# P08R60.net
KiCad netlist of a schematic drawn in EAGLE
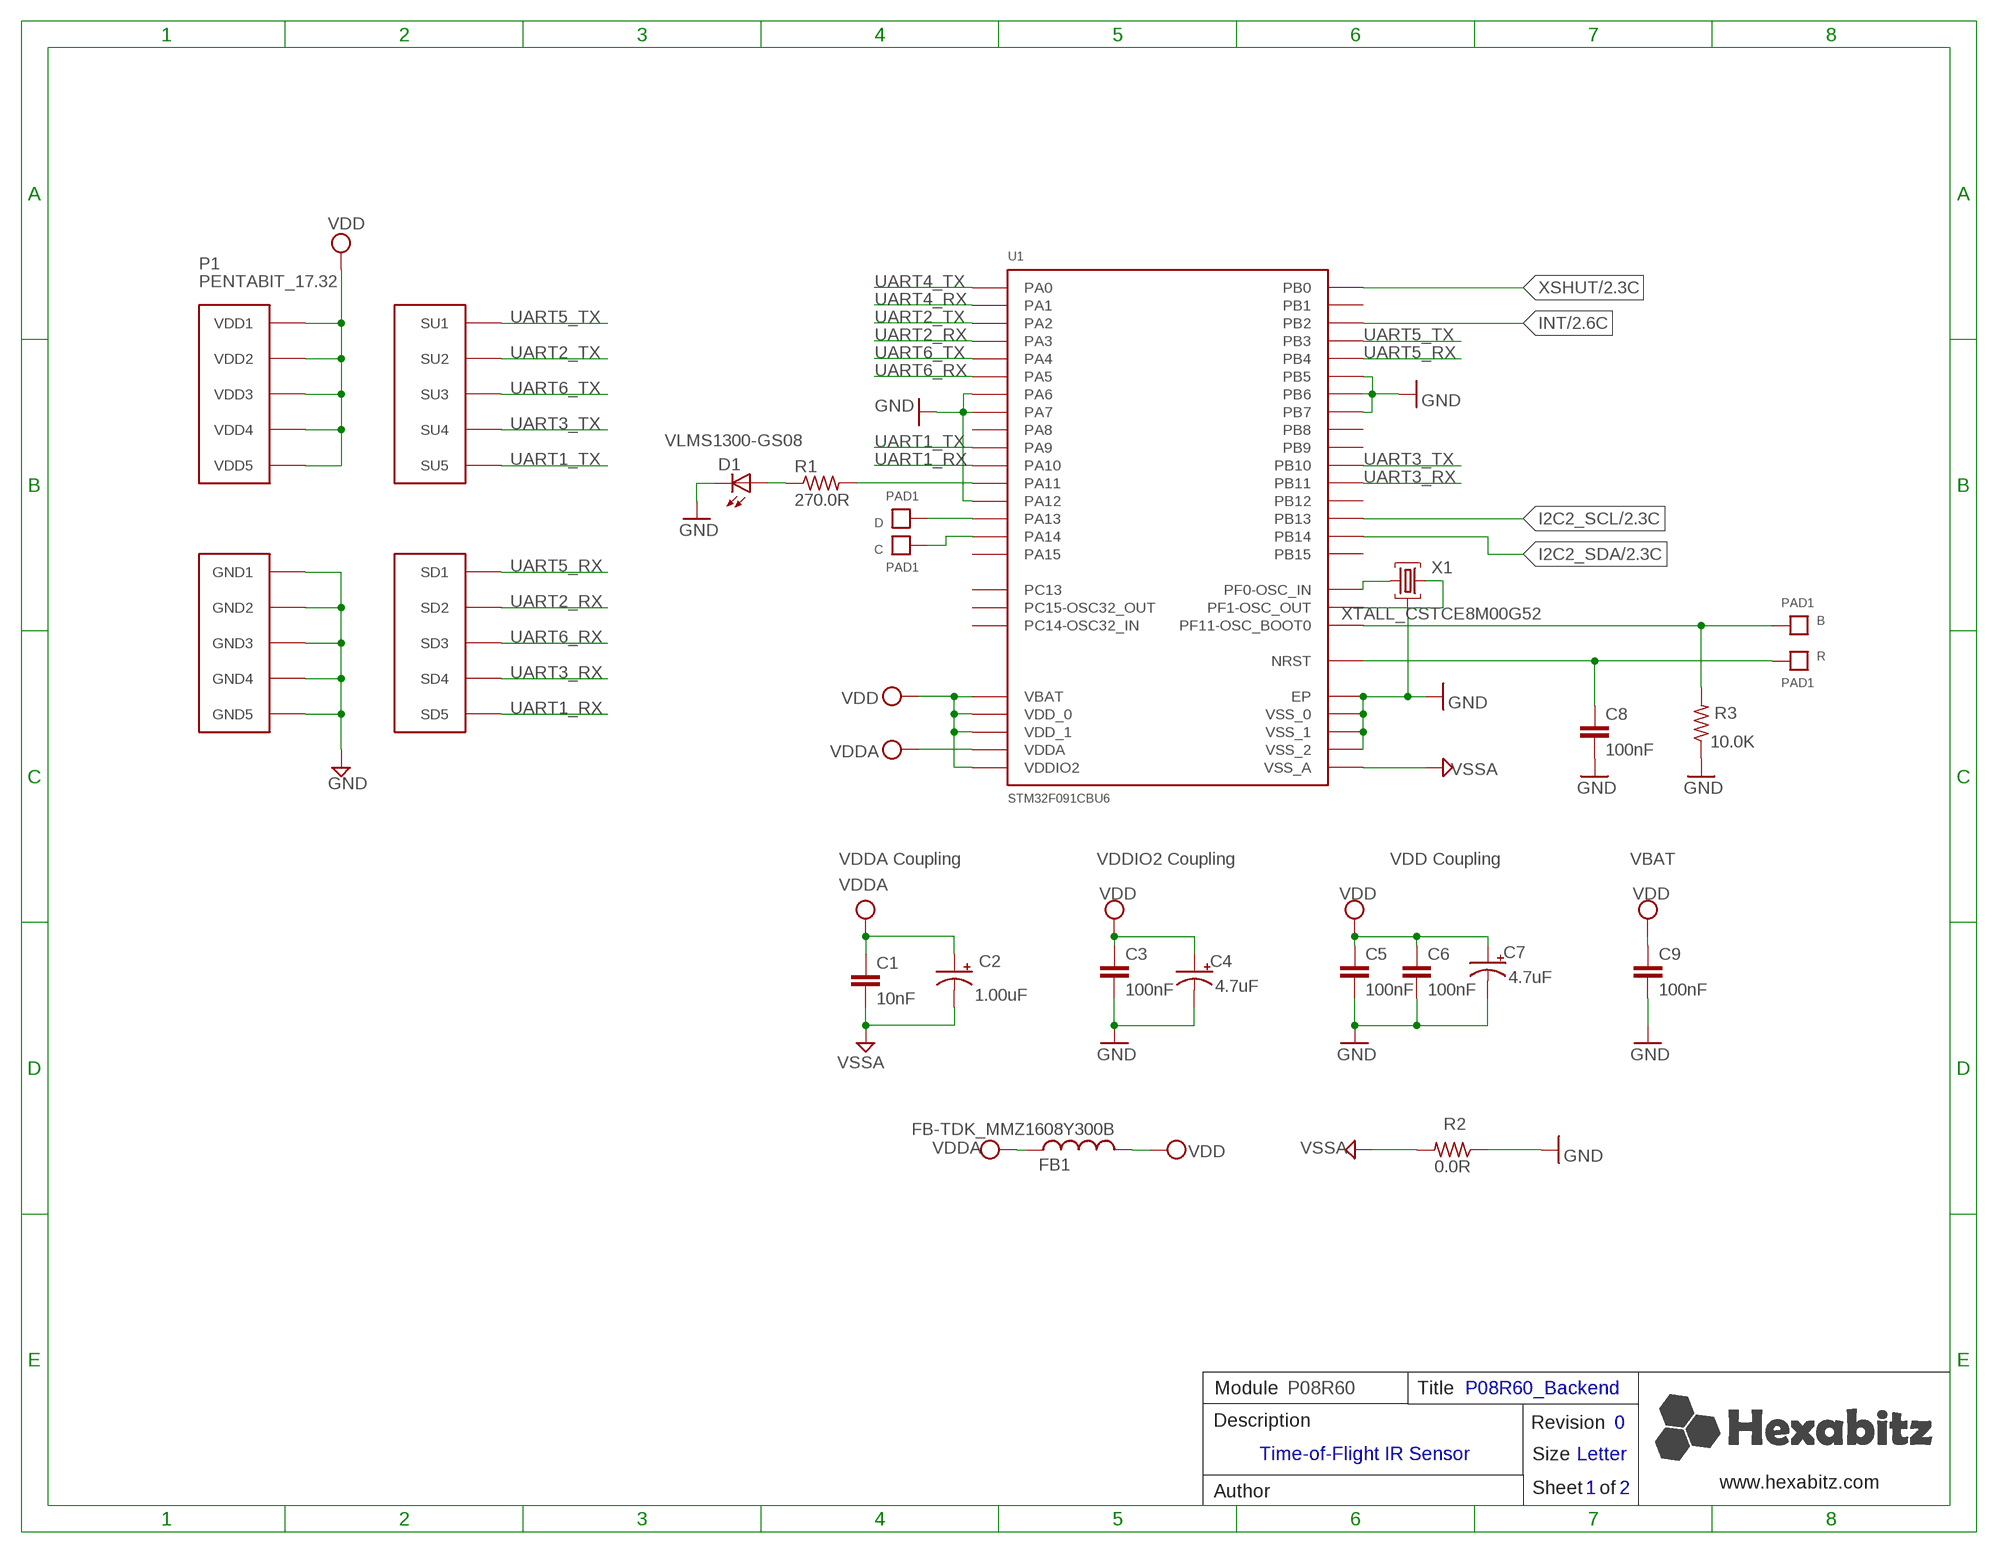
[diagram p0: schematic, sheet 1]
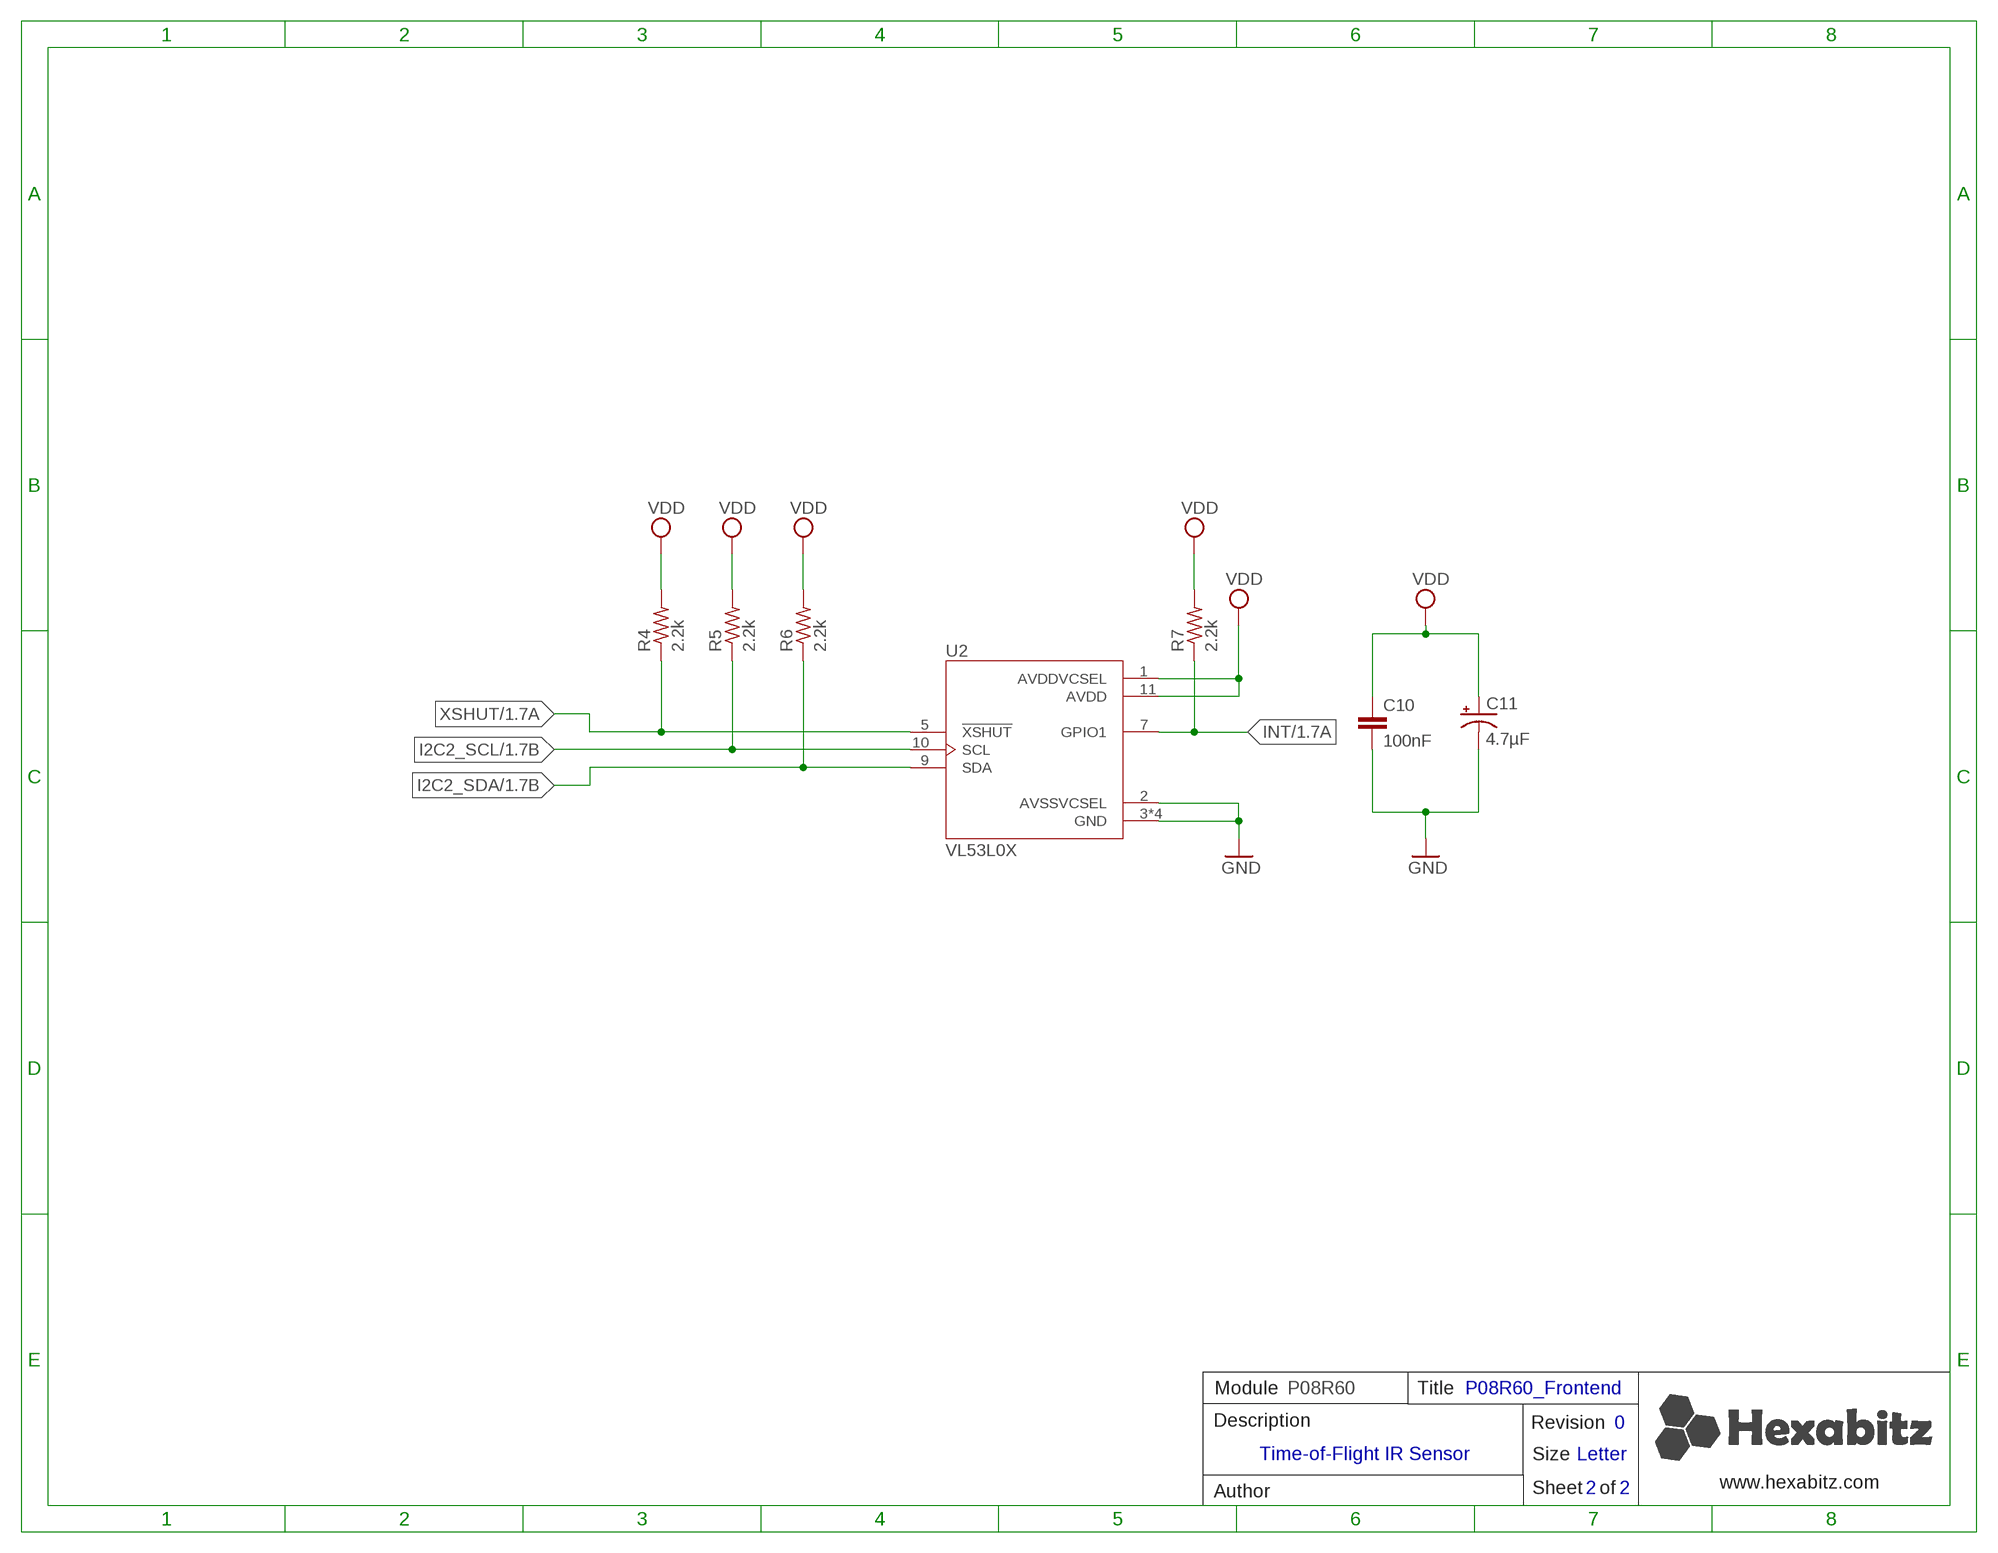
[diagram p1: schematic, sheet 2]

(export (version "E")
  (design (tool "Eeschema 10.0.6"))
  (components
    (comp (ref "C10")
      (value "100nF")
      (footprint "eagle-import:C-0603")
      (fields
        (field (name "MFN") "KEMET")
        (field (name "MPN") "C0603C104K8RACTU")
        (field (name "OCTOPART_URL") "https://octopart.com/0603yc104k4t2a-avx+interconnect+%2F+elco-8120651")
        (field (name "TOLERANCE") "±10%")
        (field (name "VOLTAGE_RATING") "16.0 V")
      )
      (libsource (lib "eagle-import") (part "C-0603"))
    )
    (comp (ref "C11")
      (value "4.7uF")
      (footprint "eagle-import:C-0805")
      (fields
        (field (name "CAPACITANCE") "4.7µF")
        (field (name "MFN") "Murata")
        (field (name "MPN") "GRM21BC81E475KA12L")
        (field (name "OCTOPART_URL") "https://octopart.com/grm21bc81e475ka12l-murata-10331911?r=sp&s=RY3qZSD8T6mG6TC9CHI5qQ")
        (field (name "TOLERANCE") "10%")
        (field (name "VOLTAGE_RATING") "25V")
      )
      (libsource (lib "eagle-import") (part "C-0805"))
    )
    (comp (ref "R4")
      (value "2.2k")
      (footprint "eagle-import:R-0603")
      (fields
        (field (name "MFN") "Vishay")
        (field (name "MPN") "CRCW06032K20FKEA")
        (field (name "OCTOPART_URL") "https://octopart.com/crcw06032k20fkea-vishay-40018987")
        (field (name "TOLERANCE") "±1%")
      )
      (libsource (lib "eagle-import") (part "R-0603"))
    )
    (comp (ref "R5")
      (value "2.2k")
      (footprint "eagle-import:R-0603")
      (fields
        (field (name "MFN") "Vishay")
        (field (name "MPN") "CRCW06032K20FKEA")
        (field (name "OCTOPART_URL") "https://octopart.com/crcw06032k20fkea-vishay-40018987")
        (field (name "TOLERANCE") "±1%")
      )
      (libsource (lib "eagle-import") (part "R-0603"))
    )
    (comp (ref "R6")
      (value "2.2k")
      (footprint "eagle-import:R-0603")
      (fields
        (field (name "MFN") "Vishay")
        (field (name "MPN") "CRCW06032K20FKEA")
        (field (name "OCTOPART_URL") "https://octopart.com/crcw06032k20fkea-vishay-40018987")
        (field (name "TOLERANCE") "±1%")
      )
      (libsource (lib "eagle-import") (part "R-0603"))
    )
    (comp (ref "R7")
      (value "2.2k")
      (footprint "eagle-import:R-0603")
      (fields
        (field (name "MFN") "Vishay")
        (field (name "MPN") "CRCW06032K20FKEA")
        (field (name "OCTOPART_URL") "https://octopart.com/crcw06032k20fkea-vishay-40018987")
        (field (name "TOLERANCE") "±1%")
      )
      (libsource (lib "eagle-import") (part "R-0603"))
    )
    (comp (ref "U2")
      (value "VL53L0X")
      (footprint "eagle-import:SENSOR_VL53L0X")
      (fields (field (name "MPN") "VL53L0CXV0DH/1"))
      (libsource (lib "eagle-import") (part "VL53L0X"))
    )
    (comp (ref "B")
      (value "PAD1")
      (footprint "eagle-import:PAD1")
      (libsource (lib "eagle-import") (part "PAD1"))
    )
    (comp (ref "C")
      (value "PAD1")
      (footprint "eagle-import:PAD1")
      (libsource (lib "eagle-import") (part "PAD1"))
    )
    (comp (ref "C1")
      (value "10nF")
      (footprint "eagle-import:C-0603")
      (fields
        (field (name "CAPACITANCE") "10nF")
        (field (name "MFN") "KEMET")
        (field (name "MPN") "C0603C103K5RACTU")
        (field (name "OCTOPART_URL") "https://octopart.com/c0603c103k5ractu-kemet-133094?r=sp&s=R_iPBxLnSmGqhkU2rIMFpg")
        (field (name "TOLERANCE") "10%")
        (field (name "VOLTAGE_RATING") "50V")
      )
      (libsource (lib "eagle-import") (part "C-0603"))
    )
    (comp (ref "C2")
      (value "1.00uF")
      (footprint "eagle-import:C-0805-POL")
      (fields
        (field (name "CAPACITANCE") "1.00uF")
        (field (name "MFN") "Yageo")
        (field (name "MPN") "CC0805KKX7R7BB105")
        (field (name "OCTOPART_URL") "https://octopart.com/cc0805kkx7r7bb105-yageo-8376555?r=sp&s=YKl1wwtkROau_X5nniH2ig")
        (field (name "TOLERANCE") "10%")
        (field (name "VOLTAGE_RATING") "16V")
      )
      (libsource (lib "eagle-import") (part "C-0805-POL"))
    )
    (comp (ref "C3")
      (value "100nF")
      (footprint "eagle-import:C-0603")
      (fields
        (field (name "CAPACITANCE") "100nF")
        (field (name "MFN") "KEMET")
        (field (name "MPN") "C0603C104K8RACTU")
        (field (name "OCTOPART_URL") "https://octopart.com/c0603c104k8ractu-kemet-145075?r=sp&s=9bS9ASSwSEqMCE9KBEQZ0g")
        (field (name "TOLERANCE") "10%")
        (field (name "VOLTAGE_RATING") "10V")
      )
      (libsource (lib "eagle-import") (part "C-0603"))
    )
    (comp (ref "C4")
      (value "4.7uF")
      (footprint "eagle-import:C-0805-POL")
      (fields
        (field (name "CAPACITANCE") "4.7uF")
        (field (name "MFN") "Murata")
        (field (name "MPN") "GRM21BC81E475KA12L")
        (field (name "OCTOPART_URL") "https://octopart.com/grm21bc81e475ka12l-murata-10331911?r=sp&s=RY3qZSD8T6mG6TC9CHI5qQ")
        (field (name "TOLERANCE") "10%")
        (field (name "VOLTAGE_RATING") "25V")
      )
      (libsource (lib "eagle-import") (part "C-0805-POL"))
    )
    (comp (ref "C5")
      (value "100nF")
      (footprint "eagle-import:C-0603")
      (fields
        (field (name "CAPACITANCE") "100nF")
        (field (name "MFN") "KEMET")
        (field (name "MPN") "C0603C104K8RACTU")
        (field (name "OCTOPART_URL") "https://octopart.com/c0603c104k8ractu-kemet-145075?r=sp&s=9bS9ASSwSEqMCE9KBEQZ0g")
        (field (name "TOLERANCE") "10%")
        (field (name "VOLTAGE_RATING") "10")
      )
      (libsource (lib "eagle-import") (part "C-0603"))
    )
    (comp (ref "C6")
      (value "100nF")
      (footprint "eagle-import:C-0603")
      (fields
        (field (name "CAPACITANCE") "100nF")
        (field (name "MFN") "KEMET")
        (field (name "MPN") "C0603C104K8RACTU")
        (field (name "OCTOPART_URL") "https://octopart.com/c0603c104k8ractu-kemet-145075?r=sp&s=9bS9ASSwSEqMCE9KBEQZ0g")
        (field (name "TOLERANCE") "10%")
        (field (name "VOLTAGE_RATING") "10V")
      )
      (libsource (lib "eagle-import") (part "C-0603"))
    )
    (comp (ref "C7")
      (value "4.7uF")
      (footprint "eagle-import:C-0805-POL")
      (fields
        (field (name "CAPACITANCE") "4.7uF")
        (field (name "MFN") "Murata")
        (field (name "MPN") "GRM21BC81E475KA12L")
        (field (name "OCTOPART_URL") "https://octopart.com/grm21bc81e475ka12l-murata-10331911?r=sp&s=RY3qZSD8T6mG6TC9CHI5qQ")
        (field (name "TOLERANCE") "10%")
        (field (name "VOLTAGE_RATING") "25V")
      )
      (libsource (lib "eagle-import") (part "C-0805-POL"))
    )
    (comp (ref "C8")
      (value "100nF")
      (footprint "eagle-import:C-0603")
      (fields
        (field (name "CAPACITANCE") "100nF")
        (field (name "MFN") "KEMET")
        (field (name "MPN") "C0603C104K8RACTU")
        (field (name "OCTOPART_URL") "https://octopart.com/c0603c104k8ractu-kemet-145075?r=sp&s=9bS9ASSwSEqMCE9KBEQZ0g")
        (field (name "TOLERANCE") "10%")
        (field (name "VOLTAGE_RATING") "10V")
      )
      (libsource (lib "eagle-import") (part "C-0603"))
    )
    (comp (ref "C9")
      (value "100nF")
      (footprint "eagle-import:C-0603")
      (fields
        (field (name "CAPACITANCE") "100nF")
        (field (name "MFN") "KEMET")
        (field (name "MPN") "C0603C104K8RACTU")
        (field (name "OCTOPART_URL") "https://octopart.com/c0603c104k8ractu-kemet-145075?r=sp&s=9bS9ASSwSEqMCE9KBEQZ0g")
        (field (name "TOLERANCE") "10V")
        (field (name "VOLTAGE_RATING") "10%")
      )
      (libsource (lib "eagle-import") (part "C-0603"))
    )
    (comp (ref "D")
      (value "PAD1")
      (footprint "eagle-import:PAD1")
      (libsource (lib "eagle-import") (part "PAD1"))
    )
    (comp (ref "D1")
      (value "VLMS1300-GS08")
      (footprint "eagle-import:VLMS1300-GS08")
      (fields
        (field (name "MFN") "Vishay")
        (field (name "MPN") "VLMS1300-GS08")
        (field (name "OCTOPART_URL") "https://octopart.com/vlms1300-gs08-vishay-21709201?r=sp&s=_gcP4_q8T1SC6PJQPTQ9yA")
      )
      (libsource (lib "eagle-import") (part "VLMS1300-GS08"))
    )
    (comp (ref "FB1")
      (value "FB-TDK_MMZ1608Y300B")
      (footprint "eagle-import:FB-TDK_MMZ1608Y300B")
      (fields
        (field (name "MFN") "TDK ")
        (field (name "MPN") "MMZ1608Y300B")
        (field (name "OCTOPART_URL") "https://octopart.com/mmz1608y300b-tdk-368280?r=sp&s=cd9_2ZEqQ9q9UNBuQgHAiA")
      )
      (libsource (lib "eagle-import") (part "FB-TDK_MMZ1608Y300B"))
    )
    (comp (ref "P1")
      (value "PENTABIT_17.32")
      (footprint "eagle-import:PENTABIT_17.32")
      (libsource (lib "eagle-import") (part "PENTABIT_?17.32"))
    )
    (comp (ref "R")
      (value "PAD1")
      (footprint "eagle-import:PAD1")
      (libsource (lib "eagle-import") (part "PAD1"))
    )
    (comp (ref "R1")
      (value "270.0R")
      (footprint "eagle-import:R-0603")
      (fields
        (field (name "MFN") "Yageo")
        (field (name "MPN") "RC0603FR-07270RL")
        (field (name "OCTOPART_URL") "https://octopart.com/search?q=RC0603FR-07270RL&start=0")
        (field (name "RESISTANCE") "270.0 Ohm")
        (field (name "TOLERANCE") "1%")
      )
      (libsource (lib "eagle-import") (part "R-0603"))
    )
    (comp (ref "R2")
      (value "0.0R")
      (footprint "eagle-import:R-0603")
      (fields
        (field (name "MFN") "Yageo")
        (field (name "MPN") "RC0603JR-070RL")
        (field (name "OCTOPART_URL") "https://octopart.com/rc0603jr-070rl-yageo-1241539?r=sp&s=X2NteqRjRNWrnx42Y0aliA")
        (field (name "RESISTANCE") "0.0 Ohm")
      )
      (libsource (lib "eagle-import") (part "R-0603"))
    )
    (comp (ref "R3")
      (value "10.0K")
      (footprint "eagle-import:R-0603")
      (fields
        (field (name "MFN") "Yageo")
        (field (name "MPN") "RC0603JR-0710KL")
        (field (name "OCTOPART_URL") "https://octopart.com/search?q=RC0603JR-0710KL&start=0")
        (field (name "RESISTANCE") "10.0K Ohm")
        (field (name "TOLERANCE") "5%")
      )
      (libsource (lib "eagle-import") (part "R-0603"))
    )
    (comp (ref "U1")
      (value "STM32F091CBU6")
      (footprint "eagle-import:STM32F091CBU6")
      (libsource (lib "eagle-import") (part "STM32F091CBU6"))
    )
    (comp (ref "X1")
      (value "XTALL_CSTCE8M00G52")
      (footprint "eagle-import:XTALL_CSTCE8M00G52")
      (fields (field (name "MPN") "CSTCE8M00G52Z-R0"))
      (libsource (lib "eagle-import") (part "XTALL_CSTCE8M00G52"))
    )
  )
  (nets
    (net (code "1") (name "GND") (class "Default")
      (node (ref "C10") (pin "2") (pinfunction "2_2") (pintype "passive"))
      (node (ref "C11") (pin "2") (pinfunction "-_2") (pintype "passive"))
      (node (ref "C3") (pin "2") (pinfunction "2_2") (pintype "passive"))
      (node (ref "C4") (pin "2") (pinfunction "-_2") (pintype "passive"))
      (node (ref "C5") (pin "2") (pinfunction "2_2") (pintype "passive"))
      (node (ref "C6") (pin "2") (pinfunction "2_2") (pintype "passive"))
      (node (ref "C7") (pin "2") (pinfunction "-_2") (pintype "passive"))
      (node (ref "C8") (pin "2") (pinfunction "2_2") (pintype "passive"))
      (node (ref "C9") (pin "2") (pinfunction "2_2") (pintype "passive"))
      (node (ref "D1") (pin "C") (pinfunction "C_C") (pintype "passive"))
      (node (ref "P1") (pin "PAD_PD10") (pinfunction "GND5_PAD_PD10") (pintype "power_in"))
      (node (ref "P1") (pin "PAD_PD6") (pinfunction "GND1_PAD_PD6") (pintype "power_in"))
      (node (ref "P1") (pin "PAD_PD7") (pinfunction "GND2_PAD_PD7") (pintype "power_in"))
      (node (ref "P1") (pin "PAD_PD8") (pinfunction "GND3_PAD_PD8") (pintype "power_in"))
      (node (ref "P1") (pin "PAD_PD9") (pinfunction "GND4_PAD_PD9") (pintype "power_in"))
      (node (ref "R2") (pin "1") (pinfunction "1_1") (pintype "passive"))
      (node (ref "R3") (pin "1") (pinfunction "1_1") (pintype "passive"))
      (node (ref "U1") (pin "EP") (pinfunction "EP_EP") (pintype "power_in"))
      (node (ref "U1") (pin "P$16") (pinfunction "PA6_P$16") (pintype "bidirectional"))
      (node (ref "U1") (pin "P$17") (pinfunction "PA7_P$17") (pintype "bidirectional"))
      (node (ref "U1") (pin "P$23") (pinfunction "VSS_0_P$23") (pintype "power_in"))
      (node (ref "U1") (pin "P$33") (pinfunction "PA12_P$33") (pintype "bidirectional"))
      (node (ref "U1") (pin "P$35") (pinfunction "VSS_1_P$35") (pintype "power_in"))
      (node (ref "U1") (pin "P$41") (pinfunction "PB5_P$41") (pintype "bidirectional"))
      (node (ref "U1") (pin "P$42") (pinfunction "PB6_P$42") (pintype "bidirectional"))
      (node (ref "U1") (pin "P$43") (pinfunction "PB7_P$43") (pintype "bidirectional"))
      (node (ref "U1") (pin "P$47") (pinfunction "VSS_2_P$47") (pintype "power_in"))
      (node (ref "U2") (pin "12") (pinfunction "GND_12") (pintype "power_in"))
      (node (ref "U2") (pin "2") (pinfunction "AVSSVCSEL_2") (pintype "power_in"))
      (node (ref "U2") (pin "3") (pinfunction "GND_3") (pintype "power_in"))
      (node (ref "U2") (pin "4") (pinfunction "GND_4") (pintype "power_in"))
      (node (ref "U2") (pin "6") (pinfunction "GND_6") (pintype "power_in"))
      (node (ref "X1") (pin "P$2") (pinfunction "2_P$2") (pintype "passive"))
    )
    (net (code "2") (name "I2C2_SCL") (class "Default")
      (node (ref "R5") (pin "1") (pinfunction "1_1") (pintype "passive"))
      (node (ref "U1") (pin "P$26") (pinfunction "PB13_P$26") (pintype "bidirectional"))
      (node (ref "U2") (pin "10") (pinfunction "SCL_10") (pintype "input"))
    )
    (net (code "3") (name "I2C2_SDA") (class "Default")
      (node (ref "R6") (pin "1") (pinfunction "1_1") (pintype "passive"))
      (node (ref "U1") (pin "P$27") (pinfunction "PB14_P$27") (pintype "bidirectional"))
      (node (ref "U2") (pin "9") (pinfunction "SDA_9") (pintype "bidirectional"))
    )
    (net (code "4") (name "INT") (class "Default")
      (node (ref "R7") (pin "1") (pinfunction "1_1") (pintype "passive"))
      (node (ref "U1") (pin "P$20") (pinfunction "PB2_P$20") (pintype "bidirectional"))
      (node (ref "U2") (pin "7") (pinfunction "GPIO1_7") (pintype "output"))
    )
    (net (code "5") (name "Net-(D1-PadA)") (class "Default")
      (node (ref "D1") (pin "A") (pinfunction "A_A") (pintype "passive"))
      (node (ref "R1") (pin "1") (pinfunction "1_1") (pintype "passive"))
    )
    (net (code "6") (name "Net-(U1-NRST)") (class "Default")
      (node (ref "C8") (pin "1") (pinfunction "1_1") (pintype "passive"))
      (node (ref "R") (pin "P$1") (pinfunction "P$1_P$1") (pintype "passive"))
      (node (ref "R") (pin "P$2") (pinfunction "P$1_P$2") (pintype "passive"))
      (node (ref "U1") (pin "P$7") (pinfunction "NRST_P$7") (pintype "passive"))
    )
    (net (code "7") (name "Net-(U1-PA11)") (class "Default")
      (node (ref "R1") (pin "2") (pinfunction "2_2") (pintype "passive"))
      (node (ref "U1") (pin "P$32") (pinfunction "PA11_P$32") (pintype "bidirectional"))
    )
    (net (code "8") (name "Net-(U1-PA13)") (class "Default")
      (node (ref "D") (pin "P$1") (pinfunction "P$1_P$1") (pintype "passive"))
      (node (ref "D") (pin "P$2") (pinfunction "P$1_P$2") (pintype "passive"))
      (node (ref "U1") (pin "P$34") (pinfunction "PA13_P$34") (pintype "bidirectional"))
    )
    (net (code "9") (name "Net-(U1-PA14)") (class "Default")
      (node (ref "C") (pin "P$1") (pinfunction "P$1_P$1") (pintype "passive"))
      (node (ref "C") (pin "P$2") (pinfunction "P$1_P$2") (pintype "passive"))
      (node (ref "U1") (pin "P$37") (pinfunction "PA14_P$37") (pintype "bidirectional"))
    )
    (net (code "10") (name "Net-(U1-PF0-OSC_IN)") (class "Default")
      (node (ref "U1") (pin "P$5") (pinfunction "PF0-OSC_IN_P$5") (pintype "bidirectional"))
      (node (ref "X1") (pin "P$1") (pinfunction "1_P$1") (pintype "passive"))
    )
    (net (code "11") (name "Net-(U1-PF1-OSC_OUT)") (class "Default")
      (node (ref "U1") (pin "P$6") (pinfunction "PF1-OSC_OUT_P$6") (pintype "bidirectional"))
      (node (ref "X1") (pin "P$3") (pinfunction "3_P$3") (pintype "passive"))
    )
    (net (code "12") (name "Net-(U1-PF11-OSC_BOOT0)") (class "Default")
      (node (ref "B") (pin "P$1") (pinfunction "P$1_P$1") (pintype "passive"))
      (node (ref "B") (pin "P$2") (pinfunction "P$1_P$2") (pintype "passive"))
      (node (ref "R3") (pin "2") (pinfunction "2_2") (pintype "passive"))
      (node (ref "U1") (pin "P$44") (pinfunction "PF11-OSC_BOOT0_P$44") (pintype "bidirectional"))
    )
    (net (code "13") (name "UART1_RX") (class "Default")
      (node (ref "P1") (pin "PAD_PD5") (pinfunction "SD5_PAD_PD5") (pintype "bidirectional"))
      (node (ref "U1") (pin "P$31") (pinfunction "PA10_P$31") (pintype "bidirectional"))
    )
    (net (code "14") (name "UART1_TX") (class "Default")
      (node (ref "P1") (pin "PAD_PU5") (pinfunction "SU5_PAD_PU5") (pintype "bidirectional"))
      (node (ref "U1") (pin "P$30") (pinfunction "PA9_P$30") (pintype "bidirectional"))
    )
    (net (code "15") (name "UART2_RX") (class "Default")
      (node (ref "P1") (pin "PAD_PD2") (pinfunction "SD2_PAD_PD2") (pintype "bidirectional"))
      (node (ref "U1") (pin "P$13") (pinfunction "PA3_P$13") (pintype "bidirectional"))
    )
    (net (code "16") (name "UART2_TX") (class "Default")
      (node (ref "P1") (pin "PAD_PU2") (pinfunction "SU2_PAD_PU2") (pintype "bidirectional"))
      (node (ref "U1") (pin "P$12") (pinfunction "PA2_P$12") (pintype "bidirectional"))
    )
    (net (code "17") (name "UART3_RX") (class "Default")
      (node (ref "P1") (pin "PAD_PD4") (pinfunction "SD4_PAD_PD4") (pintype "bidirectional"))
      (node (ref "U1") (pin "P$22") (pinfunction "PB11_P$22") (pintype "bidirectional"))
    )
    (net (code "18") (name "UART3_TX") (class "Default")
      (node (ref "P1") (pin "PAD_PU4") (pinfunction "SU4_PAD_PU4") (pintype "bidirectional"))
      (node (ref "U1") (pin "P$21") (pinfunction "PB10_P$21") (pintype "bidirectional"))
    )
    (net (code "19") (name "UART4_RX") (class "Default")
      (node (ref "U1") (pin "P$11") (pinfunction "PA1_P$11") (pintype "bidirectional"))
    )
    (net (code "20") (name "UART4_TX") (class "Default")
      (node (ref "U1") (pin "P$10") (pinfunction "PA0_P$10") (pintype "bidirectional"))
    )
    (net (code "21") (name "UART5_RX") (class "Default")
      (node (ref "P1") (pin "PAD_PD1") (pinfunction "SD1_PAD_PD1") (pintype "bidirectional"))
      (node (ref "U1") (pin "P$40") (pinfunction "PB4_P$40") (pintype "bidirectional"))
    )
    (net (code "22") (name "UART5_TX") (class "Default")
      (node (ref "P1") (pin "PAD_PU1") (pinfunction "SU1_PAD_PU1") (pintype "bidirectional"))
      (node (ref "U1") (pin "P$39") (pinfunction "PB3_P$39") (pintype "bidirectional"))
    )
    (net (code "23") (name "UART6_RX") (class "Default")
      (node (ref "P1") (pin "PAD_PD3") (pinfunction "SD3_PAD_PD3") (pintype "bidirectional"))
      (node (ref "U1") (pin "P$15") (pinfunction "PA5_P$15") (pintype "bidirectional"))
    )
    (net (code "24") (name "UART6_TX") (class "Default")
      (node (ref "P1") (pin "PAD_PU3") (pinfunction "SU3_PAD_PU3") (pintype "bidirectional"))
      (node (ref "U1") (pin "P$14") (pinfunction "PA4_P$14") (pintype "bidirectional"))
    )
    (net (code "25") (name "VDD") (class "Default")
      (node (ref "C10") (pin "1") (pinfunction "1_1") (pintype "passive"))
      (node (ref "C11") (pin "1") (pinfunction "+_1") (pintype "passive"))
      (node (ref "C3") (pin "1") (pinfunction "1_1") (pintype "passive"))
      (node (ref "C4") (pin "1") (pinfunction "+_1") (pintype "passive"))
      (node (ref "C5") (pin "1") (pinfunction "1_1") (pintype "passive"))
      (node (ref "C6") (pin "1") (pinfunction "1_1") (pintype "passive"))
      (node (ref "C7") (pin "1") (pinfunction "+_1") (pintype "passive"))
      (node (ref "C9") (pin "1") (pinfunction "1_1") (pintype "passive"))
      (node (ref "FB1") (pin "2") (pinfunction "2_2") (pintype "passive"))
      (node (ref "P1") (pin "PAD_PU10") (pinfunction "VDD5_PAD_PU10") (pintype "power_in"))
      (node (ref "P1") (pin "PAD_PU6") (pinfunction "VDD1_PAD_PU6") (pintype "power_in"))
      (node (ref "P1") (pin "PAD_PU7") (pinfunction "VDD2_PAD_PU7") (pintype "power_in"))
      (node (ref "P1") (pin "PAD_PU8") (pinfunction "VDD3_PAD_PU8") (pintype "power_in"))
      (node (ref "P1") (pin "PAD_PU9") (pinfunction "VDD4_PAD_PU9") (pintype "power_in"))
      (node (ref "R4") (pin "2") (pinfunction "2_2") (pintype "passive"))
      (node (ref "R5") (pin "2") (pinfunction "2_2") (pintype "passive"))
      (node (ref "R6") (pin "2") (pinfunction "2_2") (pintype "passive"))
      (node (ref "R7") (pin "2") (pinfunction "2_2") (pintype "passive"))
      (node (ref "U1") (pin "P$1") (pinfunction "VBAT_P$1") (pintype "power_in"))
      (node (ref "U1") (pin "P$24") (pinfunction "VDD_0_P$24") (pintype "power_in"))
      (node (ref "U1") (pin "P$36") (pinfunction "VDDIO2_P$36") (pintype "power_in"))
      (node (ref "U1") (pin "P$48") (pinfunction "VDD_1_P$48") (pintype "power_in"))
      (node (ref "U2") (pin "1") (pinfunction "AVDDVCSEL_1") (pintype "power_in"))
      (node (ref "U2") (pin "11") (pinfunction "AVDD_11") (pintype "power_in"))
    )
    (net (code "26") (name "VDDA") (class "Default")
      (node (ref "C1") (pin "1") (pinfunction "1_1") (pintype "passive"))
      (node (ref "C2") (pin "1") (pinfunction "+_1") (pintype "passive"))
      (node (ref "FB1") (pin "1") (pinfunction "1_1") (pintype "passive"))
      (node (ref "U1") (pin "P$9") (pinfunction "VDDA_P$9") (pintype "power_in"))
    )
    (net (code "27") (name "VSSA") (class "Default")
      (node (ref "C1") (pin "2") (pinfunction "2_2") (pintype "passive"))
      (node (ref "C2") (pin "2") (pinfunction "-_2") (pintype "passive"))
      (node (ref "R2") (pin "2") (pinfunction "2_2") (pintype "passive"))
      (node (ref "U1") (pin "P$8") (pinfunction "VSS_A_P$8") (pintype "power_in"))
    )
    (net (code "28") (name "XSHUT") (class "Default")
      (node (ref "R4") (pin "1") (pinfunction "1_1") (pintype "passive"))
      (node (ref "U1") (pin "P$18") (pinfunction "PB0_P$18") (pintype "bidirectional"))
      (node (ref "U2") (pin "5") (pinfunction "~{XSHUT}_5") (pintype "input"))
    )
    (net (code "29") (name "unconnected-(U1-PA8-PadP$29)") (class "Default")
      (node (ref "U1") (pin "P$29") (pinfunction "PA8_P$29") (pintype "bidirectional"))
    )
    (net (code "30") (name "unconnected-(U1-PA15-PadP$38)") (class "Default")
      (node (ref "U1") (pin "P$38") (pinfunction "PA15_P$38") (pintype "bidirectional"))
    )
    (net (code "31") (name "unconnected-(U1-PB1-PadP$19)") (class "Default")
      (node (ref "U1") (pin "P$19") (pinfunction "PB1_P$19") (pintype "bidirectional"))
    )
    (net (code "32") (name "unconnected-(U1-PB8-PadP$45)") (class "Default")
      (node (ref "U1") (pin "P$45") (pinfunction "PB8_P$45") (pintype "bidirectional"))
    )
    (net (code "33") (name "unconnected-(U1-PB9-PadP$46)") (class "Default")
      (node (ref "U1") (pin "P$46") (pinfunction "PB9_P$46") (pintype "bidirectional"))
    )
    (net (code "34") (name "unconnected-(U1-PB12-PadP$25)") (class "Default")
      (node (ref "U1") (pin "P$25") (pinfunction "PB12_P$25") (pintype "bidirectional"))
    )
    (net (code "35") (name "unconnected-(U1-PB15-PadP$28)") (class "Default")
      (node (ref "U1") (pin "P$28") (pinfunction "PB15_P$28") (pintype "bidirectional"))
    )
    (net (code "36") (name "unconnected-(U1-PC13-PadP$2)") (class "Default")
      (node (ref "U1") (pin "P$2") (pinfunction "PC13_P$2") (pintype "bidirectional"))
    )
    (net (code "37") (name "unconnected-(U1-PC14-OSC32_IN-PadP$3)") (class "Default")
      (node (ref "U1") (pin "P$3") (pinfunction "PC14-OSC32_IN_P$3") (pintype "bidirectional"))
    )
    (net (code "38") (name "unconnected-(U1-PC15-OSC32_OUT-PadP$4)") (class "Default")
      (node (ref "U1") (pin "P$4") (pinfunction "PC15-OSC32_OUT_P$4") (pintype "bidirectional"))
    )
  )
)
